# FlightPCB.net
KiCad netlist of a schematic drawn in EAGLE
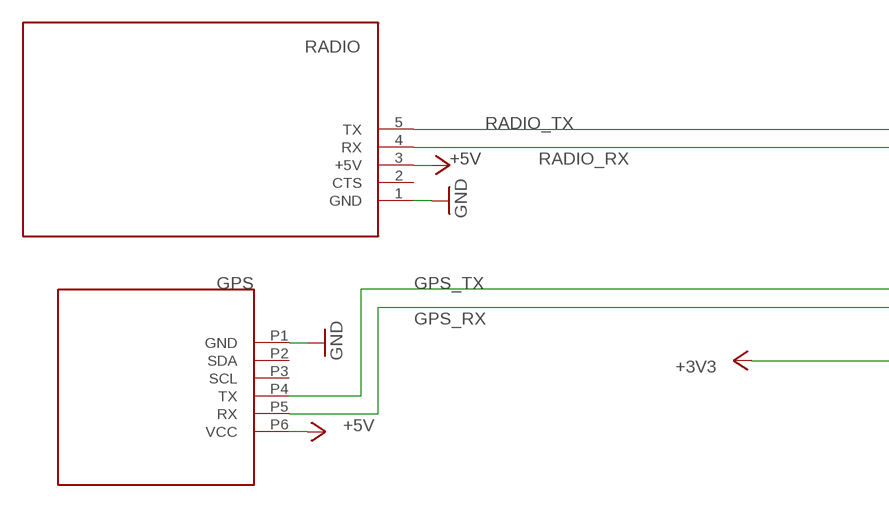
[diagram p0: schematic, sheet 1, part 1 of 2]
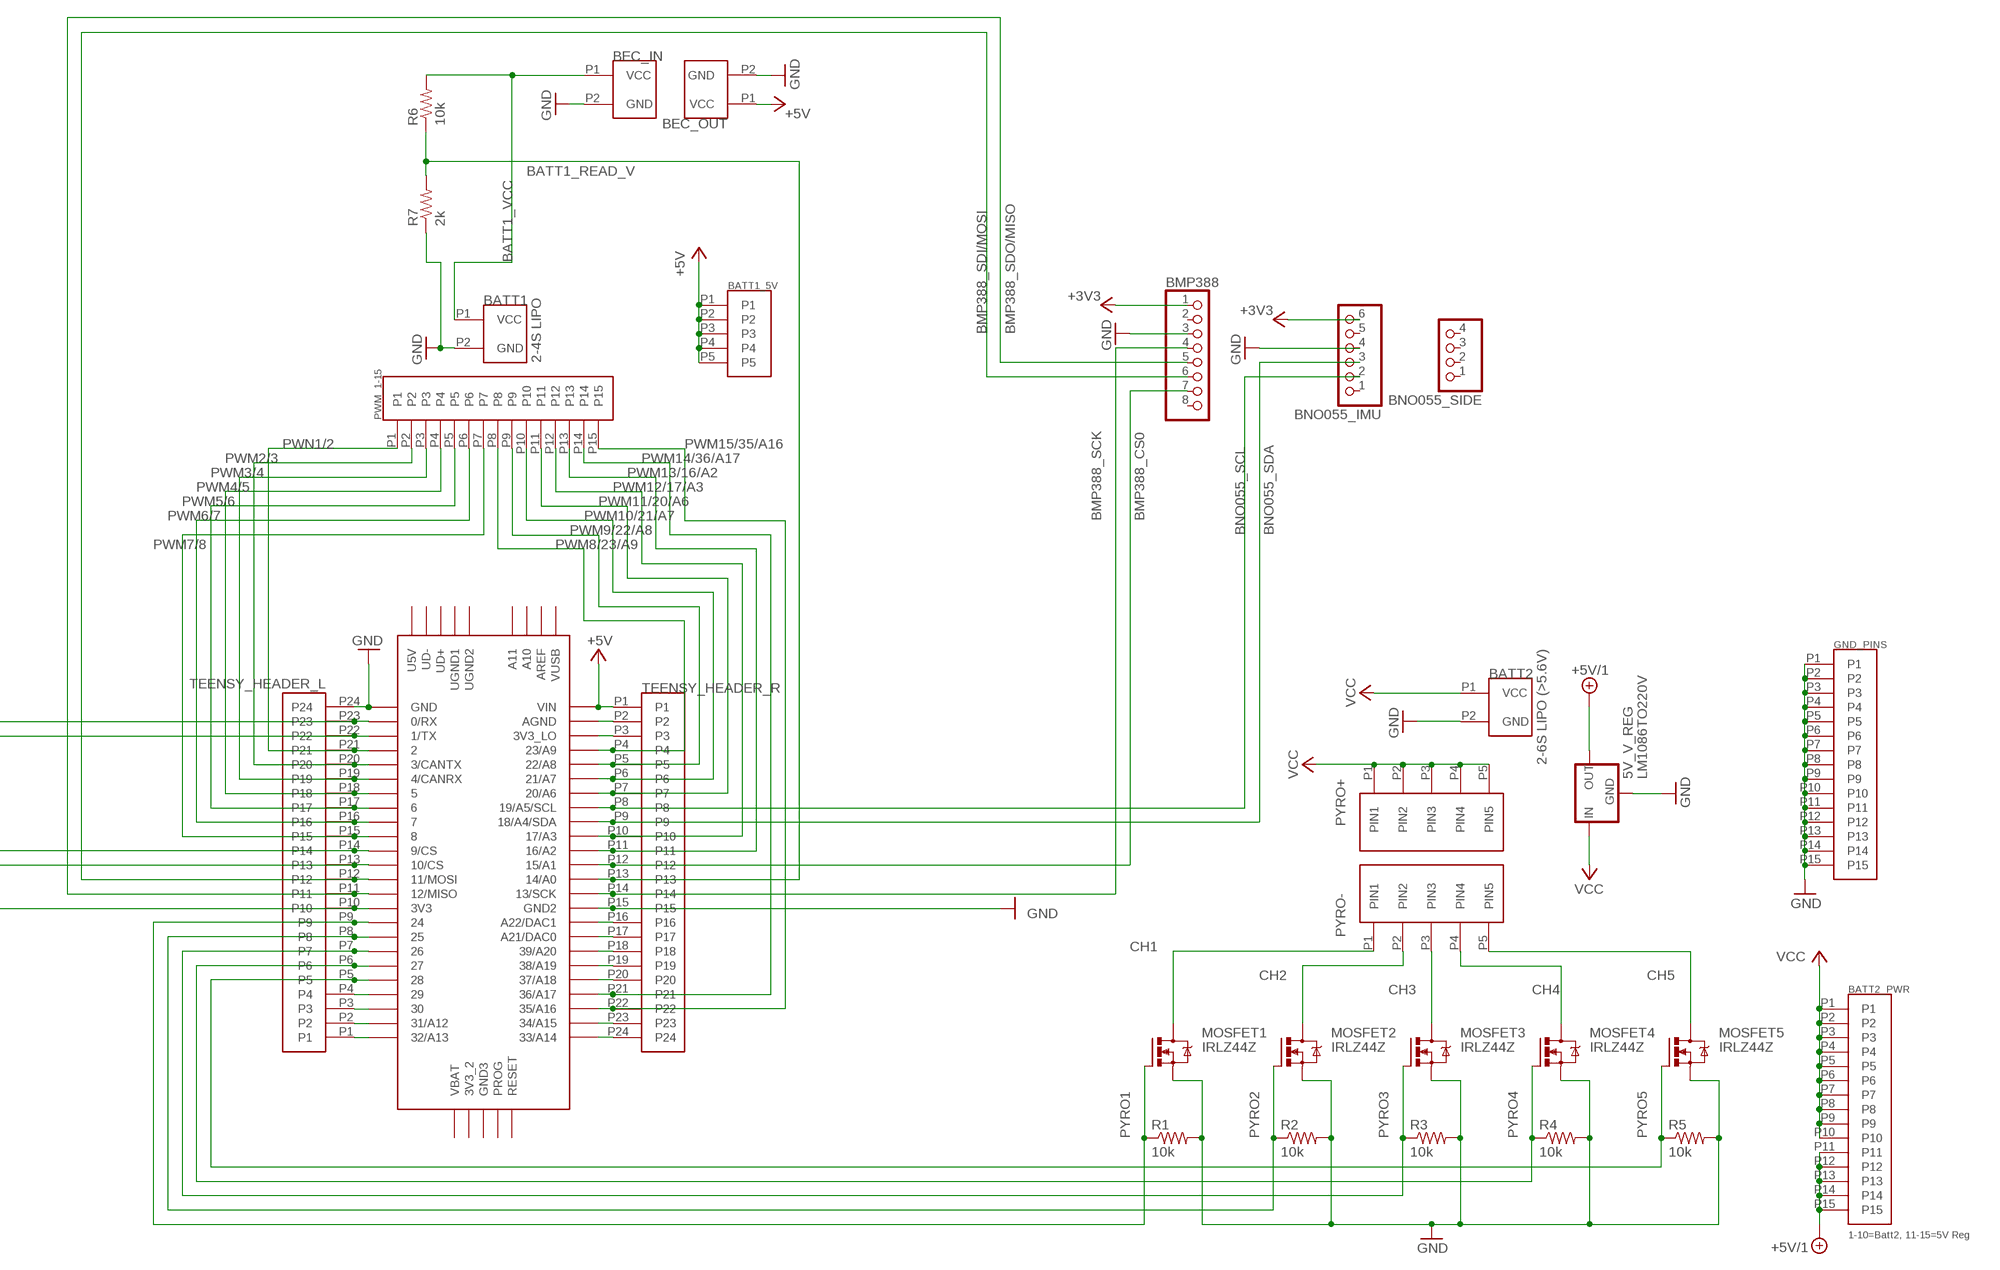
[diagram p1: schematic, sheet 1, part 2 of 2]

(export (version "E")
  (design (tool "Eeschema 10.0.6"))
  (components
    (comp (ref "5V_V_REG")
      (value "LM1086TO220V")
      (footprint "eagle-import:TO220S")
      (libsource (lib "eagle-import") (part "LM1086TO220V"))
    )
    (comp (ref "BATT1")
      (value "2-4S LIPO")
      (footprint "eagle-import:TERMINAL_BLOCK_2_PIN_5MM")
      (libsource (lib "eagle-import") (part "TERMINAL_BLOCK_2_PIN_5MM"))
    )
    (comp (ref "BATT1_5V")
      (value "PIN_HEADER_5")
      (footprint "eagle-import:PIN_HEADER_5")
      (libsource (lib "eagle-import") (part "PIN_HEADER_5"))
    )
    (comp (ref "BATT2")
      (value "2-6S LIPO (>5.6V)")
      (footprint "eagle-import:TERMINAL_BLOCK_2_PIN_5MM")
      (libsource (lib "eagle-import") (part "TERMINAL_BLOCK_2_PIN_5MM"))
    )
    (comp (ref "BATT2_PWR")
      (value "1-10=Batt2, 11-15=5V Reg")
      (footprint "eagle-import:PIN_HEADER_15")
      (libsource (lib "eagle-import") (part "PIN_HEADER_15"))
    )
    (comp (ref "BEC_IN")
      (value "TERMINAL_BLOCK_2_PIN_5MM")
      (footprint "eagle-import:TERMINAL_BLOCK_2_PIN_5MM")
      (libsource (lib "eagle-import") (part "TERMINAL_BLOCK_2_PIN_5MM"))
    )
    (comp (ref "BEC_OUT")
      (value "TERMINAL_BLOCK_2_PIN_5MM")
      (footprint "eagle-import:TERMINAL_BLOCK_2_PIN_5MM")
      (libsource (lib "eagle-import") (part "TERMINAL_BLOCK_2_PIN_5MM"))
    )
    (comp (ref "BMP388")
      (value "MICROBUILDER_HEADER-1X8ROUND")
      (footprint "eagle-import:MICROBUILDER_1X08_ROUND")
      (libsource (lib "eagle-import") (part "MICROBUILDER_HEADER-1X8ROUND"))
    )
    (comp (ref "BNO055_IMU")
      (value "MICROBUILDER_HEADER-1X6ROUND")
      (footprint "eagle-import:MICROBUILDER_1X06_ROUND")
      (libsource (lib "eagle-import") (part "MICROBUILDER_HEADER-1X6ROUND"))
    )
    (comp (ref "BNO055_SIDE")
      (value "MICROBUILDER_HEADER-1X4ROUND")
      (footprint "eagle-import:MICROBUILDER_1X04_ROUND")
      (libsource (lib "eagle-import") (part "MICROBUILDER_HEADER-1X4ROUND"))
    )
    (comp (ref "FLIGHT_COMPUTER")
      (value "TEENSY_3.5/3.6")
      (footprint "eagle-import:TEENSY_3.5_3.6")
      (libsource (lib "eagle-import") (part "TEENSY_3.5/3.6"))
    )
    (comp (ref "GND_PINS")
      (value "PIN_HEADER_15")
      (footprint "eagle-import:PIN_HEADER_15")
      (libsource (lib "eagle-import") (part "PIN_HEADER_15"))
    )
    (comp (ref "GPS")
      (value "NEO_M8N_GPS_BREAKOUT")
      (footprint "eagle-import:NEO_M8N_GPS_BREAKOUT")
      (libsource (lib "eagle-import") (part "NEO_M8N_GPS_BREAKOUT"))
    )
    (comp (ref "MOSFET1")
      (value "IRLZ44Z")
      (footprint "eagle-import:TO220BH_SIMPLE")
      (libsource (lib "eagle-import") (part "IRLZ44Z"))
    )
    (comp (ref "MOSFET2")
      (value "IRLZ44Z")
      (footprint "eagle-import:TO220BH_SIMPLE")
      (libsource (lib "eagle-import") (part "IRLZ44Z"))
    )
    (comp (ref "MOSFET3")
      (value "IRLZ44Z")
      (footprint "eagle-import:TO220BH_SIMPLE")
      (libsource (lib "eagle-import") (part "IRLZ44Z"))
    )
    (comp (ref "MOSFET4")
      (value "IRLZ44Z")
      (footprint "eagle-import:TO220BH_SIMPLE")
      (libsource (lib "eagle-import") (part "IRLZ44Z"))
    )
    (comp (ref "MOSFET5")
      (value "IRLZ44Z")
      (footprint "eagle-import:TO220BH_SIMPLE")
      (libsource (lib "eagle-import") (part "IRLZ44Z"))
    )
    (comp (ref "PWM_1-15")
      (value "PIN_HEADER_15")
      (footprint "eagle-import:PIN_HEADER_15")
      (libsource (lib "eagle-import") (part "PIN_HEADER_15"))
    )
    (comp (ref "PYRO+")
      (value "TERMINAL_BLOCK_5_PIN_5MM")
      (footprint "eagle-import:TERMINAL_BLOCK_5_PIN_5MM")
      (libsource (lib "eagle-import") (part "TERMINAL_BLOCK_5_PIN_5MM"))
    )
    (comp (ref "PYRO-")
      (value "TERMINAL_BLOCK_5_PIN_5MM")
      (footprint "eagle-import:TERMINAL_BLOCK_5_PIN_5MM")
      (libsource (lib "eagle-import") (part "TERMINAL_BLOCK_5_PIN_5MM"))
    )
    (comp (ref "R1")
      (value "10k")
      (footprint "eagle-import:0204_5")
      (libsource (lib "eagle-import") (part "R-US_0204/5"))
    )
    (comp (ref "R2")
      (value "10k")
      (footprint "eagle-import:0204_5")
      (libsource (lib "eagle-import") (part "R-US_0204/5"))
    )
    (comp (ref "R3")
      (value "10k")
      (footprint "eagle-import:0204_5")
      (libsource (lib "eagle-import") (part "R-US_0204/5"))
    )
    (comp (ref "R4")
      (value "10k")
      (footprint "eagle-import:0204_5")
      (libsource (lib "eagle-import") (part "R-US_0204/5"))
    )
    (comp (ref "R5")
      (value "10k")
      (footprint "eagle-import:0204_5")
      (libsource (lib "eagle-import") (part "R-US_0204/5"))
    )
    (comp (ref "R6")
      (value "10k")
      (footprint "eagle-import:0204_5")
      (libsource (lib "eagle-import") (part "R-US_0204/5"))
    )
    (comp (ref "R7")
      (value "2k")
      (footprint "eagle-import:0204_5")
      (libsource (lib "eagle-import") (part "R-US_0204/5"))
    )
    (comp (ref "RADIO")
      (value "RFD900")
      (footprint "eagle-import:RFD900")
      (libsource (lib "eagle-import") (part "RFD900"))
    )
    (comp (ref "TEENSY_HEADER_L")
      (value "PIN_HEADER_24_TEENSY_RAIL")
      (footprint "eagle-import:PIN_HEADER_24_TEENSY_RAIL")
      (libsource (lib "eagle-import") (part "PIN_HEADER_24_TEENSY_RAIL"))
    )
    (comp (ref "TEENSY_HEADER_R")
      (value "PIN_HEADER_24_TEENSY_RAIL")
      (footprint "eagle-import:PIN_HEADER_24_TEENSY_RAIL")
      (libsource (lib "eagle-import") (part "PIN_HEADER_24_TEENSY_RAIL"))
    )
  )
  (nets
    (net (code "1") (name "+3V3") (class "Default")
      (node (ref "BMP388") (pin "1") (pinfunction "1_1") (pintype "passive"))
      (node (ref "BNO055_IMU") (pin "6") (pinfunction "6_6") (pintype "passive"))
      (node (ref "FLIGHT_COMPUTER") (pin "3V3") (pinfunction "3V3_3V3") (pintype "bidirectional"))
      (node (ref "TEENSY_HEADER_L") (pin "P10") (pinfunction "P10_P10") (pintype "bidirectional"))
    )
    (net (code "2") (name "+5V") (class "Default")
      (node (ref "BATT1_5V") (pin "P1") (pinfunction "P1_P1") (pintype "bidirectional"))
      (node (ref "BATT1_5V") (pin "P2") (pinfunction "P2_P2") (pintype "bidirectional"))
      (node (ref "BATT1_5V") (pin "P3") (pinfunction "P3_P3") (pintype "bidirectional"))
      (node (ref "BATT1_5V") (pin "P4") (pinfunction "P4_P4") (pintype "bidirectional"))
      (node (ref "BATT1_5V") (pin "P5") (pinfunction "P5_P5") (pintype "bidirectional"))
      (node (ref "BEC_OUT") (pin "P1") (pinfunction "VCC_P1") (pintype "power_in"))
      (node (ref "FLIGHT_COMPUTER") (pin "VIN") (pinfunction "VIN_VIN") (pintype "bidirectional"))
      (node (ref "GPS") (pin "P6") (pinfunction "VCC_P6") (pintype "power_in"))
      (node (ref "RADIO") (pin "3") (pinfunction "+5V_3") (pintype "power_in"))
      (node (ref "TEENSY_HEADER_R") (pin "P1") (pinfunction "P1_P1") (pintype "bidirectional"))
    )
    (net (code "3") (name "+5V{slash}1") (class "Default")
      (node (ref "5V_V_REG") (pin "2") (pinfunction "OUT_2") (pintype "passive"))
      (node (ref "BATT2_PWR") (pin "P11") (pinfunction "P11_P11") (pintype "bidirectional"))
      (node (ref "BATT2_PWR") (pin "P12") (pinfunction "P12_P12") (pintype "bidirectional"))
      (node (ref "BATT2_PWR") (pin "P13") (pinfunction "P13_P13") (pintype "bidirectional"))
      (node (ref "BATT2_PWR") (pin "P14") (pinfunction "P14_P14") (pintype "bidirectional"))
      (node (ref "BATT2_PWR") (pin "P15") (pinfunction "P15_P15") (pintype "bidirectional"))
    )
    (net (code "4") (name "/BATT1_READ_V") (class "Default")
      (node (ref "FLIGHT_COMPUTER") (pin "14/A0") (pinfunction "14/A0_14/A0") (pintype "bidirectional"))
      (node (ref "R6") (pin "1") (pinfunction "1_1") (pintype "passive"))
      (node (ref "R7") (pin "2") (pinfunction "2_2") (pintype "passive"))
      (node (ref "TEENSY_HEADER_R") (pin "P13") (pinfunction "P13_P13") (pintype "bidirectional"))
    )
    (net (code "5") (name "/BATT1_VCC") (class "Default")
      (node (ref "BATT1") (pin "P1") (pinfunction "VCC_P1") (pintype "power_in"))
      (node (ref "BEC_IN") (pin "P1") (pinfunction "VCC_P1") (pintype "power_in"))
      (node (ref "R6") (pin "2") (pinfunction "2_2") (pintype "passive"))
    )
    (net (code "6") (name "/BMP388_CS0") (class "Default")
      (node (ref "BMP388") (pin "7") (pinfunction "7_7") (pintype "passive"))
      (node (ref "FLIGHT_COMPUTER") (pin "15/A1") (pinfunction "15/A1_15/A1") (pintype "bidirectional"))
      (node (ref "TEENSY_HEADER_R") (pin "P12") (pinfunction "P12_P12") (pintype "bidirectional"))
    )
    (net (code "7") (name "/BMP388_SCK") (class "Default")
      (node (ref "BMP388") (pin "4") (pinfunction "4_4") (pintype "passive"))
      (node (ref "FLIGHT_COMPUTER") (pin "13/SCK") (pinfunction "13/SCK_13/SCK") (pintype "bidirectional"))
      (node (ref "TEENSY_HEADER_R") (pin "P14") (pinfunction "P14_P14") (pintype "bidirectional"))
    )
    (net (code "8") (name "/BMP388_SDI{slash}MOSI") (class "Default")
      (node (ref "BMP388") (pin "6") (pinfunction "6_6") (pintype "passive"))
      (node (ref "FLIGHT_COMPUTER") (pin "11/MOSI") (pinfunction "11/MOSI_11/MOSI") (pintype "bidirectional"))
      (node (ref "TEENSY_HEADER_L") (pin "P12") (pinfunction "P12_P12") (pintype "bidirectional"))
    )
    (net (code "9") (name "/BMP388_SDO{slash}MISO") (class "Default")
      (node (ref "BMP388") (pin "5") (pinfunction "5_5") (pintype "passive"))
      (node (ref "FLIGHT_COMPUTER") (pin "12/MISO") (pinfunction "12/MISO_12/MISO") (pintype "bidirectional"))
      (node (ref "TEENSY_HEADER_L") (pin "P11") (pinfunction "P11_P11") (pintype "bidirectional"))
    )
    (net (code "10") (name "/BNO055_SCL") (class "Default")
      (node (ref "BNO055_IMU") (pin "2") (pinfunction "2_2") (pintype "passive"))
      (node (ref "FLIGHT_COMPUTER") (pin "19/A5/SCL") (pinfunction "19/A5/SCL_19/A5/SCL") (pintype "bidirectional"))
      (node (ref "TEENSY_HEADER_R") (pin "P8") (pinfunction "P8_P8") (pintype "bidirectional"))
    )
    (net (code "11") (name "/BNO055_SDA") (class "Default")
      (node (ref "BNO055_IMU") (pin "3") (pinfunction "3_3") (pintype "passive"))
      (node (ref "FLIGHT_COMPUTER") (pin "18/A4/SDA") (pinfunction "18/A4/SDA_18/A4/SDA") (pintype "bidirectional"))
      (node (ref "TEENSY_HEADER_R") (pin "P9") (pinfunction "P9_P9") (pintype "bidirectional"))
    )
    (net (code "12") (name "/CH1") (class "Default")
      (node (ref "MOSFET1") (pin "D") (pinfunction "D_D") (pintype "passive"))
      (node (ref "PYRO-") (pin "P1") (pinfunction "PIN1_P1") (pintype "bidirectional"))
    )
    (net (code "13") (name "/CH2") (class "Default")
      (node (ref "MOSFET2") (pin "D") (pinfunction "D_D") (pintype "passive"))
      (node (ref "PYRO-") (pin "P2") (pinfunction "PIN2_P2") (pintype "bidirectional"))
    )
    (net (code "14") (name "/CH3") (class "Default")
      (node (ref "MOSFET3") (pin "D") (pinfunction "D_D") (pintype "passive"))
      (node (ref "PYRO-") (pin "P3") (pinfunction "PIN3_P3") (pintype "bidirectional"))
    )
    (net (code "15") (name "/CH4") (class "Default")
      (node (ref "MOSFET4") (pin "D") (pinfunction "D_D") (pintype "passive"))
      (node (ref "PYRO-") (pin "P4") (pinfunction "PIN4_P4") (pintype "bidirectional"))
    )
    (net (code "16") (name "/CH5") (class "Default")
      (node (ref "MOSFET5") (pin "D") (pinfunction "D_D") (pintype "passive"))
      (node (ref "PYRO-") (pin "P5") (pinfunction "PIN5_P5") (pintype "bidirectional"))
    )
    (net (code "17") (name "/GPS_RX") (class "Default")
      (node (ref "FLIGHT_COMPUTER") (pin "10/CS") (pinfunction "10/CS_10/CS") (pintype "bidirectional"))
      (node (ref "GPS") (pin "P5") (pinfunction "RX_P5") (pintype "input"))
      (node (ref "TEENSY_HEADER_L") (pin "P13") (pinfunction "P13_P13") (pintype "bidirectional"))
    )
    (net (code "18") (name "/GPS_TX") (class "Default")
      (node (ref "FLIGHT_COMPUTER") (pin "9/CS") (pinfunction "9/CS_9/CS") (pintype "bidirectional"))
      (node (ref "GPS") (pin "P4") (pinfunction "TX_P4") (pintype "output"))
      (node (ref "TEENSY_HEADER_L") (pin "P14") (pinfunction "P14_P14") (pintype "bidirectional"))
    )
    (net (code "19") (name "/PWM2{slash}3") (class "Default")
      (node (ref "FLIGHT_COMPUTER") (pin "3/CANTX") (pinfunction "3/CANTX_3/CANTX") (pintype "bidirectional"))
      (node (ref "PWM_1-15") (pin "P2") (pinfunction "P2_P2") (pintype "bidirectional"))
      (node (ref "TEENSY_HEADER_L") (pin "P20") (pinfunction "P20_P20") (pintype "bidirectional"))
    )
    (net (code "20") (name "/PWM3{slash}4") (class "Default")
      (node (ref "FLIGHT_COMPUTER") (pin "4/CANRX") (pinfunction "4/CANRX_4/CANRX") (pintype "bidirectional"))
      (node (ref "PWM_1-15") (pin "P3") (pinfunction "P3_P3") (pintype "bidirectional"))
      (node (ref "TEENSY_HEADER_L") (pin "P19") (pinfunction "P19_P19") (pintype "bidirectional"))
    )
    (net (code "21") (name "/PWM4{slash}5") (class "Default")
      (node (ref "FLIGHT_COMPUTER") (pin "5") (pinfunction "5_5") (pintype "bidirectional"))
      (node (ref "PWM_1-15") (pin "P4") (pinfunction "P4_P4") (pintype "bidirectional"))
      (node (ref "TEENSY_HEADER_L") (pin "P18") (pinfunction "P18_P18") (pintype "bidirectional"))
    )
    (net (code "22") (name "/PWM5{slash}6") (class "Default")
      (node (ref "FLIGHT_COMPUTER") (pin "6") (pinfunction "6_6") (pintype "bidirectional"))
      (node (ref "PWM_1-15") (pin "P5") (pinfunction "P5_P5") (pintype "bidirectional"))
      (node (ref "TEENSY_HEADER_L") (pin "P17") (pinfunction "P17_P17") (pintype "bidirectional"))
    )
    (net (code "23") (name "/PWM6{slash}7") (class "Default")
      (node (ref "FLIGHT_COMPUTER") (pin "7") (pinfunction "7_7") (pintype "bidirectional"))
      (node (ref "PWM_1-15") (pin "P6") (pinfunction "P6_P6") (pintype "bidirectional"))
      (node (ref "TEENSY_HEADER_L") (pin "P16") (pinfunction "P16_P16") (pintype "bidirectional"))
    )
    (net (code "24") (name "/PWM7{slash}8") (class "Default")
      (node (ref "FLIGHT_COMPUTER") (pin "8") (pinfunction "8_8") (pintype "bidirectional"))
      (node (ref "PWM_1-15") (pin "P7") (pinfunction "P7_P7") (pintype "bidirectional"))
      (node (ref "TEENSY_HEADER_L") (pin "P15") (pinfunction "P15_P15") (pintype "bidirectional"))
    )
    (net (code "25") (name "/PWM8{slash}23{slash}A9") (class "Default")
      (node (ref "FLIGHT_COMPUTER") (pin "23/A9") (pinfunction "23/A9_23/A9") (pintype "bidirectional"))
      (node (ref "PWM_1-15") (pin "P8") (pinfunction "P8_P8") (pintype "bidirectional"))
      (node (ref "TEENSY_HEADER_R") (pin "P4") (pinfunction "P4_P4") (pintype "bidirectional"))
    )
    (net (code "26") (name "/PWM9{slash}22{slash}A8") (class "Default")
      (node (ref "FLIGHT_COMPUTER") (pin "22/A8") (pinfunction "22/A8_22/A8") (pintype "bidirectional"))
      (node (ref "PWM_1-15") (pin "P9") (pinfunction "P9_P9") (pintype "bidirectional"))
      (node (ref "TEENSY_HEADER_R") (pin "P5") (pinfunction "P5_P5") (pintype "bidirectional"))
    )
    (net (code "27") (name "/PWM10{slash}21{slash}A7") (class "Default")
      (node (ref "FLIGHT_COMPUTER") (pin "21/A7") (pinfunction "21/A7_21/A7") (pintype "bidirectional"))
      (node (ref "PWM_1-15") (pin "P10") (pinfunction "P10_P10") (pintype "bidirectional"))
      (node (ref "TEENSY_HEADER_R") (pin "P6") (pinfunction "P6_P6") (pintype "bidirectional"))
    )
    (net (code "28") (name "/PWM11{slash}20{slash}A6") (class "Default")
      (node (ref "FLIGHT_COMPUTER") (pin "20/A6") (pinfunction "20/A6_20/A6") (pintype "bidirectional"))
      (node (ref "PWM_1-15") (pin "P11") (pinfunction "P11_P11") (pintype "bidirectional"))
      (node (ref "TEENSY_HEADER_R") (pin "P7") (pinfunction "P7_P7") (pintype "bidirectional"))
    )
    (net (code "29") (name "/PWM12{slash}17{slash}A3") (class "Default")
      (node (ref "FLIGHT_COMPUTER") (pin "17/A3") (pinfunction "17/A3_17/A3") (pintype "bidirectional"))
      (node (ref "PWM_1-15") (pin "P12") (pinfunction "P12_P12") (pintype "bidirectional"))
      (node (ref "TEENSY_HEADER_R") (pin "P10") (pinfunction "P10_P10") (pintype "bidirectional"))
    )
    (net (code "30") (name "/PWM13{slash}16{slash}A2") (class "Default")
      (node (ref "FLIGHT_COMPUTER") (pin "16/A2") (pinfunction "16/A2_16/A2") (pintype "bidirectional"))
      (node (ref "PWM_1-15") (pin "P13") (pinfunction "P13_P13") (pintype "bidirectional"))
      (node (ref "TEENSY_HEADER_R") (pin "P11") (pinfunction "P11_P11") (pintype "bidirectional"))
    )
    (net (code "31") (name "/PWM14{slash}36{slash}A17") (class "Default")
      (node (ref "FLIGHT_COMPUTER") (pin "36/A17") (pinfunction "36/A17_36/A17") (pintype "bidirectional"))
      (node (ref "PWM_1-15") (pin "P14") (pinfunction "P14_P14") (pintype "bidirectional"))
      (node (ref "TEENSY_HEADER_R") (pin "P21") (pinfunction "P21_P21") (pintype "bidirectional"))
    )
    (net (code "32") (name "/PWM15{slash}35{slash}A16") (class "Default")
      (node (ref "FLIGHT_COMPUTER") (pin "35/A16") (pinfunction "35/A16_35/A16") (pintype "bidirectional"))
      (node (ref "PWM_1-15") (pin "P15") (pinfunction "P15_P15") (pintype "bidirectional"))
      (node (ref "TEENSY_HEADER_R") (pin "P22") (pinfunction "P22_P22") (pintype "bidirectional"))
    )
    (net (code "33") (name "/PWN1{slash}2") (class "Default")
      (node (ref "FLIGHT_COMPUTER") (pin "2") (pinfunction "2_2") (pintype "bidirectional"))
      (node (ref "PWM_1-15") (pin "P1") (pinfunction "P1_P1") (pintype "bidirectional"))
      (node (ref "TEENSY_HEADER_L") (pin "P21") (pinfunction "P21_P21") (pintype "bidirectional"))
    )
    (net (code "34") (name "/PYRO1") (class "Default")
      (node (ref "FLIGHT_COMPUTER") (pin "24") (pinfunction "24_24") (pintype "bidirectional"))
      (node (ref "MOSFET1") (pin "G") (pinfunction "G_G") (pintype "passive"))
      (node (ref "R1") (pin "1") (pinfunction "1_1") (pintype "passive"))
      (node (ref "TEENSY_HEADER_L") (pin "P9") (pinfunction "P9_P9") (pintype "bidirectional"))
    )
    (net (code "35") (name "/PYRO2") (class "Default")
      (node (ref "FLIGHT_COMPUTER") (pin "25") (pinfunction "25_25") (pintype "bidirectional"))
      (node (ref "MOSFET2") (pin "G") (pinfunction "G_G") (pintype "passive"))
      (node (ref "R2") (pin "1") (pinfunction "1_1") (pintype "passive"))
      (node (ref "TEENSY_HEADER_L") (pin "P8") (pinfunction "P8_P8") (pintype "bidirectional"))
    )
    (net (code "36") (name "/PYRO3") (class "Default")
      (node (ref "FLIGHT_COMPUTER") (pin "26") (pinfunction "26_26") (pintype "bidirectional"))
      (node (ref "MOSFET3") (pin "G") (pinfunction "G_G") (pintype "passive"))
      (node (ref "R3") (pin "1") (pinfunction "1_1") (pintype "passive"))
      (node (ref "TEENSY_HEADER_L") (pin "P7") (pinfunction "P7_P7") (pintype "bidirectional"))
    )
    (net (code "37") (name "/PYRO4") (class "Default")
      (node (ref "FLIGHT_COMPUTER") (pin "27") (pinfunction "27_27") (pintype "bidirectional"))
      (node (ref "MOSFET4") (pin "G") (pinfunction "G_G") (pintype "passive"))
      (node (ref "R4") (pin "1") (pinfunction "1_1") (pintype "passive"))
      (node (ref "TEENSY_HEADER_L") (pin "P6") (pinfunction "P6_P6") (pintype "bidirectional"))
    )
    (net (code "38") (name "/PYRO5") (class "Default")
      (node (ref "FLIGHT_COMPUTER") (pin "28") (pinfunction "28_28") (pintype "bidirectional"))
      (node (ref "MOSFET5") (pin "G") (pinfunction "G_G") (pintype "passive"))
      (node (ref "R5") (pin "1") (pinfunction "1_1") (pintype "passive"))
      (node (ref "TEENSY_HEADER_L") (pin "P5") (pinfunction "P5_P5") (pintype "bidirectional"))
    )
    (net (code "39") (name "/RADIO_RX") (class "Default")
      (node (ref "FLIGHT_COMPUTER") (pin "1/TX") (pinfunction "1/TX_1/TX") (pintype "bidirectional"))
      (node (ref "RADIO") (pin "4") (pinfunction "RX_4") (pintype "input"))
      (node (ref "TEENSY_HEADER_L") (pin "P22") (pinfunction "P22_P22") (pintype "bidirectional"))
    )
    (net (code "40") (name "/RADIO_TX") (class "Default")
      (node (ref "FLIGHT_COMPUTER") (pin "0/RX") (pinfunction "0/RX_0/RX") (pintype "bidirectional"))
      (node (ref "RADIO") (pin "5") (pinfunction "TX_5") (pintype "output"))
      (node (ref "TEENSY_HEADER_L") (pin "P23") (pinfunction "P23_P23") (pintype "bidirectional"))
    )
    (net (code "41") (name "GND") (class "Default")
      (node (ref "5V_V_REG") (pin "1") (pinfunction "GND_1") (pintype "input"))
      (node (ref "BATT1") (pin "P2") (pinfunction "GND_P2") (pintype "power_in"))
      (node (ref "BATT2") (pin "P2") (pinfunction "GND_P2") (pintype "power_in"))
      (node (ref "BEC_IN") (pin "P2") (pinfunction "GND_P2") (pintype "power_in"))
      (node (ref "BEC_OUT") (pin "P2") (pinfunction "GND_P2") (pintype "power_in"))
      (node (ref "BMP388") (pin "3") (pinfunction "3_3") (pintype "passive"))
      (node (ref "BNO055_IMU") (pin "4") (pinfunction "4_4") (pintype "passive"))
      (node (ref "FLIGHT_COMPUTER") (pin "GND") (pinfunction "GND_GND") (pintype "bidirectional"))
      (node (ref "FLIGHT_COMPUTER") (pin "GND2") (pinfunction "GND2_GND2") (pintype "bidirectional"))
      (node (ref "GND_PINS") (pin "P1") (pinfunction "P1_P1") (pintype "bidirectional"))
      (node (ref "GND_PINS") (pin "P10") (pinfunction "P10_P10") (pintype "bidirectional"))
      (node (ref "GND_PINS") (pin "P11") (pinfunction "P11_P11") (pintype "bidirectional"))
      (node (ref "GND_PINS") (pin "P12") (pinfunction "P12_P12") (pintype "bidirectional"))
      (node (ref "GND_PINS") (pin "P13") (pinfunction "P13_P13") (pintype "bidirectional"))
      (node (ref "GND_PINS") (pin "P14") (pinfunction "P14_P14") (pintype "bidirectional"))
      (node (ref "GND_PINS") (pin "P15") (pinfunction "P15_P15") (pintype "bidirectional"))
      (node (ref "GND_PINS") (pin "P2") (pinfunction "P2_P2") (pintype "bidirectional"))
      (node (ref "GND_PINS") (pin "P3") (pinfunction "P3_P3") (pintype "bidirectional"))
      (node (ref "GND_PINS") (pin "P4") (pinfunction "P4_P4") (pintype "bidirectional"))
      (node (ref "GND_PINS") (pin "P5") (pinfunction "P5_P5") (pintype "bidirectional"))
      (node (ref "GND_PINS") (pin "P6") (pinfunction "P6_P6") (pintype "bidirectional"))
      (node (ref "GND_PINS") (pin "P7") (pinfunction "P7_P7") (pintype "bidirectional"))
      (node (ref "GND_PINS") (pin "P8") (pinfunction "P8_P8") (pintype "bidirectional"))
      (node (ref "GND_PINS") (pin "P9") (pinfunction "P9_P9") (pintype "bidirectional"))
      (node (ref "GPS") (pin "P1") (pinfunction "GND_P1") (pintype "power_in"))
      (node (ref "MOSFET1") (pin "S") (pinfunction "S_S") (pintype "passive"))
      (node (ref "MOSFET2") (pin "S") (pinfunction "S_S") (pintype "passive"))
      (node (ref "MOSFET3") (pin "S") (pinfunction "S_S") (pintype "passive"))
      (node (ref "MOSFET4") (pin "S") (pinfunction "S_S") (pintype "passive"))
      (node (ref "MOSFET5") (pin "S") (pinfunction "S_S") (pintype "passive"))
      (node (ref "R1") (pin "2") (pinfunction "2_2") (pintype "passive"))
      (node (ref "R2") (pin "2") (pinfunction "2_2") (pintype "passive"))
      (node (ref "R3") (pin "2") (pinfunction "2_2") (pintype "passive"))
      (node (ref "R4") (pin "2") (pinfunction "2_2") (pintype "passive"))
      (node (ref "R5") (pin "2") (pinfunction "2_2") (pintype "passive"))
      (node (ref "R7") (pin "1") (pinfunction "1_1") (pintype "passive"))
      (node (ref "RADIO") (pin "1") (pinfunction "GND_1") (pintype "power_in"))
      (node (ref "TEENSY_HEADER_L") (pin "P24") (pinfunction "P24_P24") (pintype "bidirectional"))
      (node (ref "TEENSY_HEADER_R") (pin "P15") (pinfunction "P15_P15") (pintype "bidirectional"))
    )
    (net (code "42") (name "Net-(FLIGHT_COMPUTER-A21{slash}DAC0)") (class "Default")
      (node (ref "FLIGHT_COMPUTER") (pin "21/DAC0") (pinfunction "A21/DAC0_21/DAC0") (pintype "bidirectional"))
      (node (ref "TEENSY_HEADER_R") (pin "P17") (pinfunction "P17_P17") (pintype "bidirectional"))
    )
    (net (code "43") (name "Net-(FLIGHT_COMPUTER-Pad3V3_LO)") (class "Default")
      (node (ref "FLIGHT_COMPUTER") (pin "3V3_LO") (pinfunction "3V3_LO_3V3_LO") (pintype "bidirectional"))
      (node (ref "TEENSY_HEADER_R") (pin "P3") (pinfunction "P3_P3") (pintype "bidirectional"))
    )
    (net (code "44") (name "Net-(FLIGHT_COMPUTER-Pad29)") (class "Default")
      (node (ref "FLIGHT_COMPUTER") (pin "29") (pinfunction "29_29") (pintype "bidirectional"))
      (node (ref "TEENSY_HEADER_L") (pin "P4") (pinfunction "P4_P4") (pintype "bidirectional"))
    )
    (net (code "45") (name "Net-(FLIGHT_COMPUTER-Pad30)") (class "Default")
      (node (ref "FLIGHT_COMPUTER") (pin "30") (pinfunction "30_30") (pintype "bidirectional"))
      (node (ref "TEENSY_HEADER_L") (pin "P3") (pinfunction "P3_P3") (pintype "bidirectional"))
    )
    (net (code "46") (name "Net-(FLIGHT_COMPUTER-Pad31{slash}A12)") (class "Default")
      (node (ref "FLIGHT_COMPUTER") (pin "31/A12") (pinfunction "31/A12_31/A12") (pintype "bidirectional"))
      (node (ref "TEENSY_HEADER_L") (pin "P2") (pinfunction "P2_P2") (pintype "bidirectional"))
    )
    (net (code "47") (name "Net-(FLIGHT_COMPUTER-Pad32{slash}A13)") (class "Default")
      (node (ref "FLIGHT_COMPUTER") (pin "32/A13") (pinfunction "32/A13_32/A13") (pintype "bidirectional"))
      (node (ref "TEENSY_HEADER_L") (pin "P1") (pinfunction "P1_P1") (pintype "bidirectional"))
    )
    (net (code "48") (name "Net-(FLIGHT_COMPUTER-Pad33{slash}A14)") (class "Default")
      (node (ref "FLIGHT_COMPUTER") (pin "33/A14") (pinfunction "33/A14_33/A14") (pintype "bidirectional"))
      (node (ref "TEENSY_HEADER_R") (pin "P24") (pinfunction "P24_P24") (pintype "bidirectional"))
    )
    (net (code "49") (name "Net-(FLIGHT_COMPUTER-Pad34{slash}A15)") (class "Default")
      (node (ref "FLIGHT_COMPUTER") (pin "34/A15") (pinfunction "34/A15_34/A15") (pintype "bidirectional"))
      (node (ref "TEENSY_HEADER_R") (pin "P23") (pinfunction "P23_P23") (pintype "bidirectional"))
    )
    (net (code "50") (name "Net-(FLIGHT_COMPUTER-Pad37{slash}A18)") (class "Default")
      (node (ref "FLIGHT_COMPUTER") (pin "37/A18") (pinfunction "37/A18_37/A18") (pintype "bidirectional"))
      (node (ref "TEENSY_HEADER_R") (pin "P20") (pinfunction "P20_P20") (pintype "bidirectional"))
    )
    (net (code "51") (name "Net-(FLIGHT_COMPUTER-Pad38{slash}A19)") (class "Default")
      (node (ref "FLIGHT_COMPUTER") (pin "38/A19") (pinfunction "38/A19_38/A19") (pintype "bidirectional"))
      (node (ref "TEENSY_HEADER_R") (pin "P19") (pinfunction "P19_P19") (pintype "bidirectional"))
    )
    (net (code "52") (name "Net-(FLIGHT_COMPUTER-Pad39{slash}A20)") (class "Default")
      (node (ref "FLIGHT_COMPUTER") (pin "39/A20") (pinfunction "39/A20_39/A20") (pintype "bidirectional"))
      (node (ref "TEENSY_HEADER_R") (pin "P18") (pinfunction "P18_P18") (pintype "bidirectional"))
    )
    (net (code "53") (name "Net-(FLIGHT_COMPUTER-PadA22{slash}DAC1)") (class "Default")
      (node (ref "FLIGHT_COMPUTER") (pin "A22/DAC1") (pinfunction "A22/DAC1_A22/DAC1") (pintype "bidirectional"))
      (node (ref "TEENSY_HEADER_R") (pin "P16") (pinfunction "P16_P16") (pintype "bidirectional"))
    )
    (net (code "54") (name "Net-(FLIGHT_COMPUTER-PadAGND)") (class "Default")
      (node (ref "FLIGHT_COMPUTER") (pin "AGND") (pinfunction "AGND_AGND") (pintype "bidirectional"))
      (node (ref "TEENSY_HEADER_R") (pin "P2") (pinfunction "P2_P2") (pintype "bidirectional"))
    )
    (net (code "55") (name "VCC") (class "Default")
      (node (ref "5V_V_REG") (pin "3") (pinfunction "IN_3") (pintype "input"))
      (node (ref "BATT2") (pin "P1") (pinfunction "VCC_P1") (pintype "power_in"))
      (node (ref "BATT2_PWR") (pin "P1") (pinfunction "P1_P1") (pintype "bidirectional"))
      (node (ref "BATT2_PWR") (pin "P10") (pinfunction "P10_P10") (pintype "bidirectional"))
      (node (ref "BATT2_PWR") (pin "P2") (pinfunction "P2_P2") (pintype "bidirectional"))
      (node (ref "BATT2_PWR") (pin "P3") (pinfunction "P3_P3") (pintype "bidirectional"))
      (node (ref "BATT2_PWR") (pin "P4") (pinfunction "P4_P4") (pintype "bidirectional"))
      (node (ref "BATT2_PWR") (pin "P5") (pinfunction "P5_P5") (pintype "bidirectional"))
      (node (ref "BATT2_PWR") (pin "P6") (pinfunction "P6_P6") (pintype "bidirectional"))
      (node (ref "BATT2_PWR") (pin "P7") (pinfunction "P7_P7") (pintype "bidirectional"))
      (node (ref "BATT2_PWR") (pin "P8") (pinfunction "P8_P8") (pintype "bidirectional"))
      (node (ref "BATT2_PWR") (pin "P9") (pinfunction "P9_P9") (pintype "bidirectional"))
      (node (ref "PYRO+") (pin "P1") (pinfunction "PIN1_P1") (pintype "bidirectional"))
      (node (ref "PYRO+") (pin "P2") (pinfunction "PIN2_P2") (pintype "bidirectional"))
      (node (ref "PYRO+") (pin "P3") (pinfunction "PIN3_P3") (pintype "bidirectional"))
      (node (ref "PYRO+") (pin "P4") (pinfunction "PIN4_P4") (pintype "bidirectional"))
      (node (ref "PYRO+") (pin "P5") (pinfunction "PIN5_P5") (pintype "bidirectional"))
    )
    (net (code "56") (name "unconnected-(BMP388-Pad2)") (class "Default")
      (node (ref "BMP388") (pin "2") (pinfunction "2_2") (pintype "passive"))
    )
    (net (code "57") (name "unconnected-(BMP388-Pad8)") (class "Default")
      (node (ref "BMP388") (pin "8") (pinfunction "8_8") (pintype "passive"))
    )
    (net (code "58") (name "unconnected-(BNO055_IMU-Pad1)") (class "Default")
      (node (ref "BNO055_IMU") (pin "1") (pinfunction "1_1") (pintype "passive"))
    )
    (net (code "59") (name "unconnected-(BNO055_IMU-Pad5)") (class "Default")
      (node (ref "BNO055_IMU") (pin "5") (pinfunction "5_5") (pintype "passive"))
    )
    (net (code "60") (name "unconnected-(BNO055_SIDE-Pad1)") (class "Default")
      (node (ref "BNO055_SIDE") (pin "1") (pinfunction "1_1") (pintype "passive"))
    )
    (net (code "61") (name "unconnected-(BNO055_SIDE-Pad2)") (class "Default")
      (node (ref "BNO055_SIDE") (pin "2") (pinfunction "2_2") (pintype "passive"))
    )
    (net (code "62") (name "unconnected-(BNO055_SIDE-Pad3)") (class "Default")
      (node (ref "BNO055_SIDE") (pin "3") (pinfunction "3_3") (pintype "passive"))
    )
    (net (code "63") (name "unconnected-(BNO055_SIDE-Pad4)") (class "Default")
      (node (ref "BNO055_SIDE") (pin "4") (pinfunction "4_4") (pintype "passive"))
    )
    (net (code "64") (name "unconnected-(FLIGHT_COMPUTER-Pad3V3_2)") (class "Default")
      (node (ref "FLIGHT_COMPUTER") (pin "3V3_2") (pinfunction "3V3_2_3V3_2") (pintype "bidirectional"))
    )
    (net (code "65") (name "unconnected-(FLIGHT_COMPUTER-PadA10)") (class "Default")
      (node (ref "FLIGHT_COMPUTER") (pin "A10") (pinfunction "A10_A10") (pintype "bidirectional"))
    )
    (net (code "66") (name "unconnected-(FLIGHT_COMPUTER-PadA11)") (class "Default")
      (node (ref "FLIGHT_COMPUTER") (pin "A11") (pinfunction "A11_A11") (pintype "bidirectional"))
    )
    (net (code "67") (name "unconnected-(FLIGHT_COMPUTER-PadAREF)") (class "Default")
      (node (ref "FLIGHT_COMPUTER") (pin "AREF") (pinfunction "AREF_AREF") (pintype "bidirectional"))
    )
    (net (code "68") (name "unconnected-(FLIGHT_COMPUTER-PadGND3)") (class "Default")
      (node (ref "FLIGHT_COMPUTER") (pin "GND3") (pinfunction "GND3_GND3") (pintype "bidirectional"))
    )
    (net (code "69") (name "unconnected-(FLIGHT_COMPUTER-PadPROG)") (class "Default")
      (node (ref "FLIGHT_COMPUTER") (pin "PROG") (pinfunction "PROG_PROG") (pintype "bidirectional"))
    )
    (net (code "70") (name "unconnected-(FLIGHT_COMPUTER-PadRESET)") (class "Default")
      (node (ref "FLIGHT_COMPUTER") (pin "RESET") (pinfunction "RESET_RESET") (pintype "bidirectional"))
    )
    (net (code "71") (name "unconnected-(FLIGHT_COMPUTER-PadU5V)") (class "Default")
      (node (ref "FLIGHT_COMPUTER") (pin "U5V") (pinfunction "U5V_U5V") (pintype "bidirectional"))
    )
    (net (code "72") (name "unconnected-(FLIGHT_COMPUTER-PadUD+)") (class "Default")
      (node (ref "FLIGHT_COMPUTER") (pin "UD+") (pinfunction "UD+_UD+") (pintype "bidirectional"))
    )
    (net (code "73") (name "unconnected-(FLIGHT_COMPUTER-PadUD-)") (class "Default")
      (node (ref "FLIGHT_COMPUTER") (pin "UD-") (pinfunction "UD-_UD-") (pintype "bidirectional"))
    )
    (net (code "74") (name "unconnected-(FLIGHT_COMPUTER-PadUGND1)") (class "Default")
      (node (ref "FLIGHT_COMPUTER") (pin "UGND1") (pinfunction "UGND1_UGND1") (pintype "bidirectional"))
    )
    (net (code "75") (name "unconnected-(FLIGHT_COMPUTER-PadUGND2)") (class "Default")
      (node (ref "FLIGHT_COMPUTER") (pin "UGND2") (pinfunction "UGND2_UGND2") (pintype "bidirectional"))
    )
    (net (code "76") (name "unconnected-(FLIGHT_COMPUTER-PadVBAT)") (class "Default")
      (node (ref "FLIGHT_COMPUTER") (pin "VBAT") (pinfunction "VBAT_VBAT") (pintype "bidirectional"))
    )
    (net (code "77") (name "unconnected-(FLIGHT_COMPUTER-PadVUSB)") (class "Default")
      (node (ref "FLIGHT_COMPUTER") (pin "VUSB") (pinfunction "VUSB_VUSB") (pintype "bidirectional"))
    )
    (net (code "78") (name "unconnected-(GPS-SCL-PadP3)") (class "Default")
      (node (ref "GPS") (pin "P3") (pinfunction "SCL_P3") (pintype "no_connect"))
    )
    (net (code "79") (name "unconnected-(GPS-SDA-PadP2)") (class "Default")
      (node (ref "GPS") (pin "P2") (pinfunction "SDA_P2") (pintype "no_connect"))
    )
    (net (code "80") (name "unconnected-(RADIO-CTS-Pad2)") (class "Default")
      (node (ref "RADIO") (pin "2") (pinfunction "CTS_2") (pintype "no_connect"))
    )
  )
)
